# 02_USB2UART.net
KiCad netlist of a schematic drawn in Altium Designer
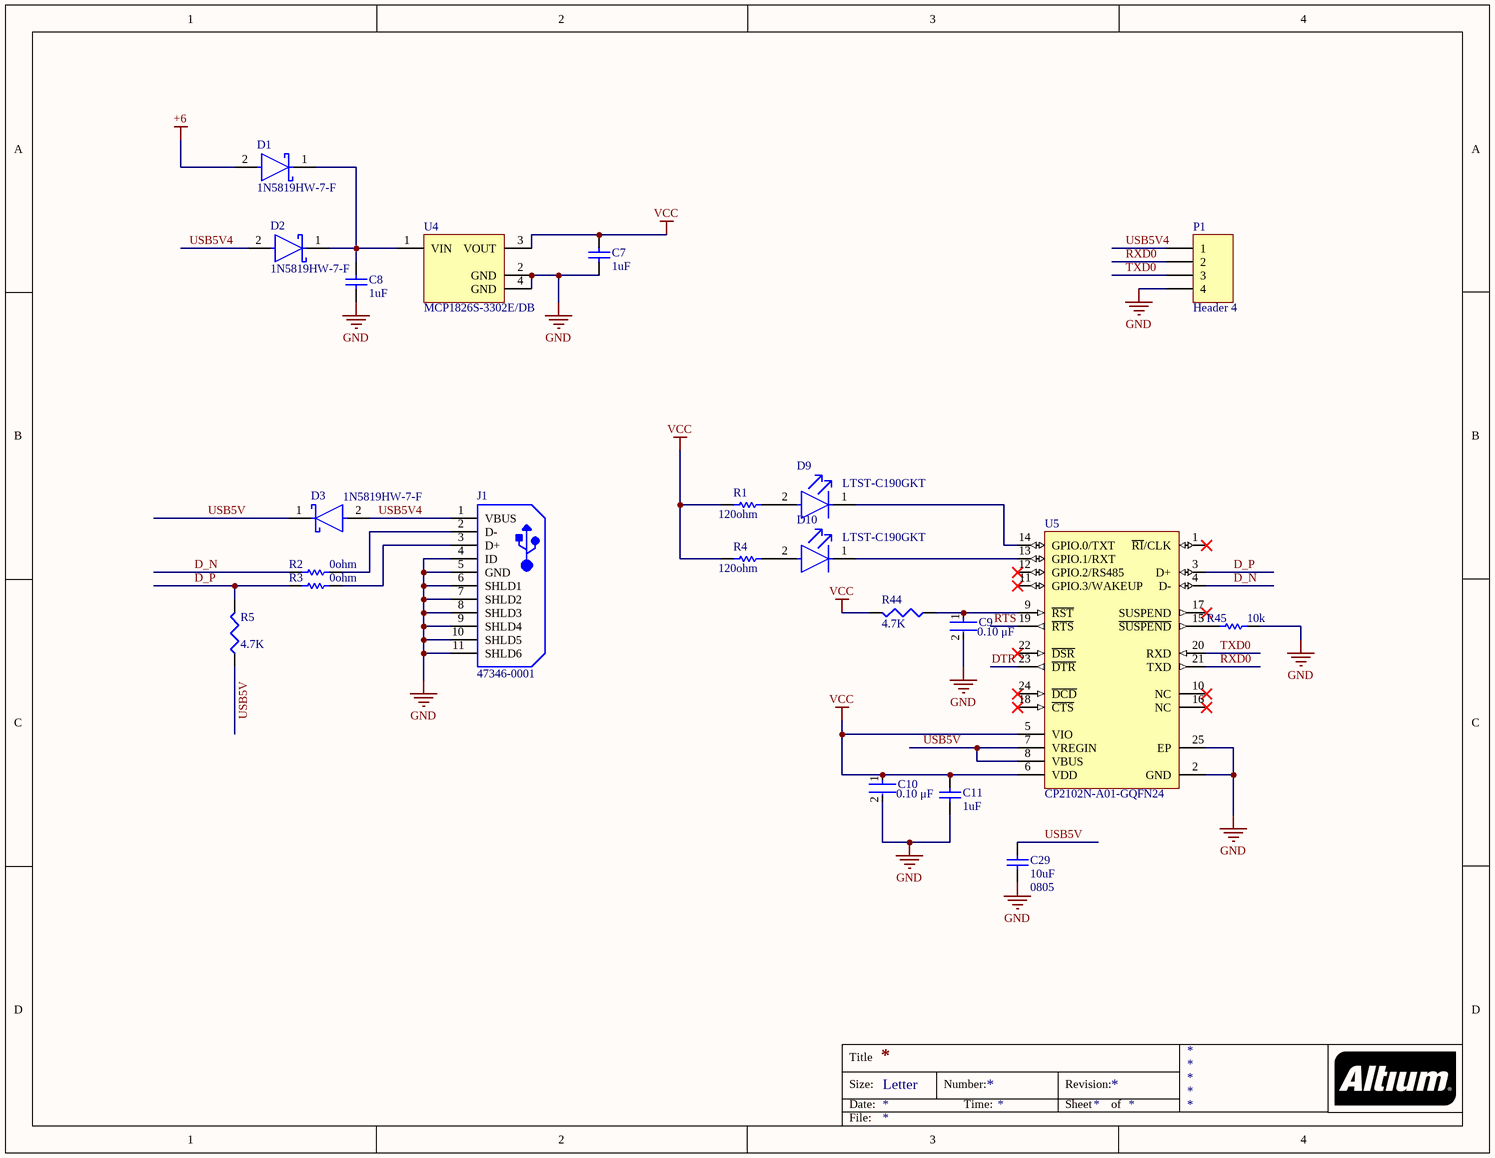
[diagram p0: 02_USB2UART.SchDoc]

(export (version "E")
  (design (tool "Eeschema 10.0.6"))
  (components
    (comp (ref "C7")
      (value "1uF")
      (footprint "CAPC1608X87X35LL15T15")
      (fields (field (name "MANUFACTURER") "Kemet") (field (name "PART NUMBER") "C0603C101J1GACTU"))
      (libsource (lib "Altium Content Vault") (part "CAP"))
    )
    (comp (ref "C8")
      (value "1uF")
      (footprint "CAPC1608X87X35LL15T15")
      (fields (field (name "MANUFACTURER") "Kemet") (field (name "PART NUMBER") "C0603C101J1GACTU"))
      (libsource (lib "Altium Content Vault") (part "CAP"))
    )
    (comp (ref "C9")
      (value "C0603C104M4RAC7411")
      (footprint "FP-C0603C-CF-MFG")
      (description "CAP CER 0.1UF 16V X7R 0603")
      (fields
        (field (name "TOLERANCE") "0.2")
        (field (name "CAPACITANCE") "0.10 μF")
        (field (name "MANUFACTURER") "KEMET")
      )
      (libsource (lib "Altium Content Vault") (part "b4654b650e69147ec39a6b967a45e02"))
    )
    (comp (ref "C10")
      (value "C0603C104M4RAC7411")
      (footprint "FP-C0603C-CF-MFG")
      (description "CAP CER 0.1UF 16V X7R 0603")
      (fields
        (field (name "TOLERANCE") "0.2")
        (field (name "CAPACITANCE") "0.10 μF")
        (field (name "MANUFACTURER") "KEMET")
      )
      (libsource (lib "Altium Content Vault") (part "b4654b650e69147ec39a6b967a45e02"))
    )
    (comp (ref "C11")
      (value "1uF")
      (footprint "CAPC1608X87X35LL15T15")
      (fields (field (name "MANUFACTURER") "Kemet") (field (name "PART NUMBER") "C0603C101J1GACTU"))
      (libsource (lib "Altium Content Vault") (part "CAP"))
    )
    (comp (ref "C29")
      (value "10uF")
      (footprint "CAPC2013X135X50LL10T20")
      (fields
        (field (name "MANUFACTURER") "Murata")
        (field (name "PART NUMBER") "GRM21BR61C106KE15L")
        (field (name "PACKAGE") "0805")
      )
      (libsource (lib "Altium Content Vault") (part "CAP"))
    )
    (comp (ref "D1")
      (value "1N5819HW-7-F")
      (footprint "FP-SOD123-MFG")
      (description "DIODE SCHOTTKY 40V 1A SOD123")
      (fields
        (field (name "OCTOPART") "https://octopart.com/1n5819hw-7-f-diodes+inc.-323197")
        (field (name "MANUFACTURER") "Diodes Inc")
      )
      (libsource (lib "Altium Content Vault") (part "1d6ec82d83fb6aee721767c19dac4b9"))
    )
    (comp (ref "D2")
      (value "1N5819HW-7-F")
      (footprint "FP-SOD123-MFG")
      (description "DIODE SCHOTTKY 40V 1A SOD123")
      (fields
        (field (name "OCTOPART") "https://octopart.com/1n5819hw-7-f-diodes+inc.-323197")
        (field (name "MANUFACTURER") "Diodes Inc")
      )
      (libsource (lib "Altium Content Vault") (part "1d6ec82d83fb6aee721767c19dac4b9"))
    )
    (comp (ref "D3")
      (value "1N5819HW-7-F")
      (footprint "FP-SOD123-MFG")
      (description "DIODE SCHOTTKY 40V 1A SOD123")
      (fields
        (field (name "OCTOPART") "https://octopart.com/1n5819hw-7-f-diodes+inc.-323197")
        (field (name "MANUFACTURER") "Diodes Inc")
      )
      (libsource (lib "Altium Content Vault") (part "1d6ec82d83fb6aee721767c19dac4b9"))
    )
    (comp (ref "D9")
      (value "LTST-C190GKT")
      (footprint "FP-LTST-C190GKT-MFG")
      (description "LED GREEN CLEAR CHIP SMD")
      (fields (field (name "VOLTAGE") "2V"))
      (libsource (lib "Altium Content Vault") (part "8706943c75ba83719d021d2fdc84c58"))
    )
    (comp (ref "D10")
      (value "LTST-C190GKT")
      (footprint "FP-LTST-C190GKT-MFG")
      (description "LED GREEN CLEAR CHIP SMD")
      (fields (field (name "VOLTAGE") "2V"))
      (libsource (lib "Altium Content Vault") (part "8706943c75ba83719d021d2fdc84c58"))
    )
    (comp (ref "J1")
      (value "47346-0001")
      (footprint "MOLX-47346-0001-5_V")
      (description "Micro-USB B Receptacle with Flange, -30 to 85 degC, 5-Pin SMD, RoHS, Tape and Reel")
      (fields (field (name "MANUFACTURER") "Molex"))
      (libsource (lib "Altium Content Vault") (part "MOLX-47346-0001-5"))
    )
    (comp (ref "P1")
      (value "Header 4")
      (footprint "HDR1X4")
      (description "Header, 4-Pin")
      (fields (field (name "PUBLISHER") "Altium Limited"))
      (libsource (lib "Miscellaneous Connectors") (part "Header 4"))
    )
    (comp (ref "R1")
      (value "120ohm")
      (footprint "RESC1608X55X30NL20T20")
      (fields (field (name "PART NUMBER") "ERA-3AEB121V") (field (name "MANUFACTURER") "Panasonic"))
      (libsource (lib "Altium Content Vault") (part "RES"))
    )
    (comp (ref "R2")
      (value "0ohm")
      (footprint "RESC1608X55X25ML10T15")
      (description "Chip Resistor, 0 Ohm, +/- 5%, 0.1 W, -55 to 155 degC, 0603 (1608 Metric), RoHS, Tape and Reel")
      (fields (field (name "TOLERANCE") "5%") (field (name "MANUFACTURER") "Yageo"))
      (libsource (lib "Altium Content Vault") (part "RES-2"))
    )
    (comp (ref "R3")
      (value "0ohm")
      (footprint "RESC1608X55X25ML10T15")
      (description "Chip Resistor, 0 Ohm, +/- 5%, 0.1 W, -55 to 155 degC, 0603 (1608 Metric), RoHS, Tape and Reel")
      (fields (field (name "TOLERANCE") "5%") (field (name "MANUFACTURER") "Yageo"))
      (libsource (lib "Altium Content Vault") (part "RES-2"))
    )
    (comp (ref "R4")
      (value "120ohm")
      (footprint "RESC1608X55X30NL20T20")
      (fields (field (name "PART NUMBER") "ERA-3AEB121V") (field (name "MANUFACTURER") "Panasonic"))
      (libsource (lib "Altium Content Vault") (part "RES"))
    )
    (comp (ref "R5")
      (value "4.7K")
      (footprint "J1-0603")
      (description "Resistor")
      (fields (field (name "Comment") "4.7k") (field (name "PUBLISHER") "Altium Limited"))
      (libsource (lib "Miscellaneous Devices") (part "Res3"))
    )
    (comp (ref "R44")
      (value "4.7K")
      (footprint "J1-0603")
      (description "Resistor")
      (fields (field (name "Comment") "4.7k") (field (name "PUBLISHER") "Altium Limited"))
      (libsource (lib "Miscellaneous Devices") (part "Res3"))
    )
    (comp (ref "R45")
      (value "10k")
      (footprint "RESC1609X55X30LL15T15")
      (description "Chip Resistor, 10 KOhm, +/- 1%, 0.1 W, -55 to 155 degC, 0603 (1608 Metric), RoHS, Tape and Reel")
      (fields (field (name "TOLERANCE") "1%") (field (name "MANUFACTURER") "Panasonic"))
      (libsource (lib "Altium Content Vault") (part "RES-2"))
    )
    (comp (ref "U4")
      (value "MCP1826S-3302E/DB")
      (footprint "SOT-223-DB3_L")
      (description "1000 mA, Low Voltage, Low Quiescent Current LDO Regulator, 3-Pin SOT-223, Extended Temperature")
      (libsource (lib "Altium Content Vault") (part "PM-LINEREG-MCP1826-IL4"))
    )
    (comp (ref "U5")
      (value "CP2102N-A01-GQFN24")
      (footprint "SLAB-QFN-24-2550x2550TP_A_V")
      (description "USBXpress(TM) Family, 4 GPIOs, 2.2 to 3.6 V, -40 to 85 degC, 24-Pin QFN, RoHS")
      (fields (field (name "MANUFACTURER") "Silicon Labs"))
      (libsource (lib "Altium Content Vault") (part "SLAB-CP2102N-QFN-24"))
    )
  )
  (nets
    (net (code "1") (name "+6") (class "Default")
      (node (ref "D1") (pin "2") (pinfunction "A_2") (pintype "passive"))
    )
    (net (code "2") (name "/DTR") (class "Default")
      (node (ref "U5") (pin "23") (pinfunction "~{DTR}_23") (pintype "output"))
    )
    (net (code "3") (name "/D_N") (class "Default")
      (node (ref "R2") (pin "1") (pinfunction "1_1") (pintype "passive"))
      (node (ref "U5") (pin "4") (pinfunction "D-_4") (pintype "bidirectional"))
    )
    (net (code "4") (name "/D_P") (class "Default")
      (node (ref "R3") (pin "1") (pinfunction "1_1") (pintype "passive"))
      (node (ref "R5") (pin "2") (pinfunction "2_2") (pintype "passive"))
      (node (ref "U5") (pin "3") (pinfunction "D+_3") (pintype "bidirectional"))
    )
    (net (code "5") (name "/RTS") (class "Default")
      (node (ref "U5") (pin "19") (pinfunction "~{RTS}_19") (pintype "output"))
    )
    (net (code "6") (name "/RXD0") (class "Default")
      (node (ref "P1") (pin "2") (pinfunction "2_2") (pintype "passive"))
      (node (ref "U5") (pin "21") (pinfunction "TXD_21") (pintype "output"))
    )
    (net (code "7") (name "/TXD0") (class "Default")
      (node (ref "P1") (pin "3") (pinfunction "3_3") (pintype "passive"))
      (node (ref "U5") (pin "20") (pinfunction "RXD_20") (pintype "input"))
    )
    (net (code "8") (name "/USB5V") (class "Default")
      (node (ref "C29") (pin "2") (pinfunction "2_2") (pintype "passive"))
      (node (ref "D3") (pin "1") (pinfunction "C_1") (pintype "passive"))
      (node (ref "R5") (pin "1") (pinfunction "1_1") (pintype "passive"))
      (node (ref "U5") (pin "7") (pinfunction "VREGIN_7") (pintype "power_in"))
      (node (ref "U5") (pin "8") (pinfunction "VBUS_8") (pintype "power_in"))
    )
    (net (code "9") (name "/USB5V4") (class "Default")
      (node (ref "D2") (pin "2") (pinfunction "A_2") (pintype "passive"))
      (node (ref "D3") (pin "2") (pinfunction "A_2") (pintype "passive"))
      (node (ref "J1") (pin "1") (pinfunction "VBUS_1") (pintype "passive"))
      (node (ref "P1") (pin "1") (pinfunction "1_1") (pintype "passive"))
    )
    (net (code "10") (name "GND") (class "Default")
      (node (ref "C10") (pin "2") (pinfunction "2_2") (pintype "passive"))
      (node (ref "C11") (pin "1") (pinfunction "1_1") (pintype "passive"))
      (node (ref "C29") (pin "1") (pinfunction "1_1") (pintype "passive"))
      (node (ref "C7") (pin "1") (pinfunction "1_1") (pintype "passive"))
      (node (ref "C8") (pin "1") (pinfunction "1_1") (pintype "passive"))
      (node (ref "C9") (pin "2") (pinfunction "2_2") (pintype "passive"))
      (node (ref "J1") (pin "10") (pinfunction "SHLD5_10") (pintype "passive"))
      (node (ref "J1") (pin "11") (pinfunction "SHLD6_11") (pintype "passive"))
      (node (ref "J1") (pin "4") (pinfunction "ID_4") (pintype "passive"))
      (node (ref "J1") (pin "5") (pinfunction "GND_5") (pintype "passive"))
      (node (ref "J1") (pin "6") (pinfunction "SHLD1_6") (pintype "passive"))
      (node (ref "J1") (pin "7") (pinfunction "SHLD2_7") (pintype "passive"))
      (node (ref "J1") (pin "8") (pinfunction "SHLD3_8") (pintype "passive"))
      (node (ref "J1") (pin "9") (pinfunction "SHLD4_9") (pintype "passive"))
      (node (ref "P1") (pin "4") (pinfunction "4_4") (pintype "passive"))
      (node (ref "R45") (pin "2") (pinfunction "2_2") (pintype "passive"))
      (node (ref "U4") (pin "2") (pinfunction "GND_2") (pintype "power_in"))
      (node (ref "U4") (pin "4") (pinfunction "GND_4") (pintype "power_in"))
      (node (ref "U5") (pin "2") (pinfunction "GND_2") (pintype "power_in"))
      (node (ref "U5") (pin "25") (pinfunction "EP_25") (pintype "power_in"))
    )
    (net (code "11") (name "Net-(D1-C)") (class "Default")
      (node (ref "C8") (pin "2") (pinfunction "2_2") (pintype "passive"))
      (node (ref "D1") (pin "1") (pinfunction "C_1") (pintype "passive"))
      (node (ref "D2") (pin "1") (pinfunction "C_1") (pintype "passive"))
      (node (ref "U4") (pin "1") (pinfunction "VIN_1") (pintype "power_in"))
    )
    (net (code "12") (name "Net-(D9-A)") (class "Default")
      (node (ref "D9") (pin "2") (pinfunction "A_2") (pintype "passive"))
      (node (ref "R1") (pin "2") (pinfunction "2_2") (pintype "passive"))
    )
    (net (code "13") (name "Net-(D9-C)") (class "Default")
      (node (ref "D9") (pin "1") (pinfunction "C_1") (pintype "passive"))
      (node (ref "U5") (pin "14") (pinfunction "GPIO.0/TXT_14") (pintype "bidirectional"))
    )
    (net (code "14") (name "Net-(D10-A)") (class "Default")
      (node (ref "D10") (pin "2") (pinfunction "A_2") (pintype "passive"))
      (node (ref "R4") (pin "2") (pinfunction "2_2") (pintype "passive"))
    )
    (net (code "15") (name "Net-(D10-C)") (class "Default")
      (node (ref "D10") (pin "1") (pinfunction "C_1") (pintype "passive"))
      (node (ref "U5") (pin "13") (pinfunction "GPIO.1/RXT_13") (pintype "bidirectional"))
    )
    (net (code "16") (name "Net-(J1-D+)") (class "Default")
      (node (ref "J1") (pin "3") (pinfunction "D+_3") (pintype "passive"))
      (node (ref "R3") (pin "2") (pinfunction "2_2") (pintype "passive"))
    )
    (net (code "17") (name "Net-(J1-D-)") (class "Default")
      (node (ref "J1") (pin "2") (pinfunction "D-_2") (pintype "passive"))
      (node (ref "R2") (pin "2") (pinfunction "2_2") (pintype "passive"))
    )
    (net (code "18") (name "Net-(U5-~{RST})") (class "Default")
      (node (ref "C9") (pin "1") (pinfunction "1_1") (pintype "passive"))
      (node (ref "R44") (pin "1") (pinfunction "1_1") (pintype "passive"))
      (node (ref "U5") (pin "9") (pinfunction "~{RST}_9") (pintype "input"))
    )
    (net (code "19") (name "Net-(U5-~{SUSPEND})") (class "Default")
      (node (ref "R45") (pin "1") (pinfunction "1_1") (pintype "passive"))
      (node (ref "U5") (pin "15") (pinfunction "~{SUSPEND}_15") (pintype "output"))
    )
    (net (code "20") (name "VCC") (class "Default")
      (node (ref "C10") (pin "1") (pinfunction "1_1") (pintype "passive"))
      (node (ref "C11") (pin "2") (pinfunction "2_2") (pintype "passive"))
      (node (ref "C7") (pin "2") (pinfunction "2_2") (pintype "passive"))
      (node (ref "R1") (pin "1") (pinfunction "1_1") (pintype "passive"))
      (node (ref "R4") (pin "1") (pinfunction "1_1") (pintype "passive"))
      (node (ref "R44") (pin "2") (pinfunction "2_2") (pintype "passive"))
      (node (ref "U4") (pin "3") (pinfunction "VOUT_3") (pintype "power_in"))
      (node (ref "U5") (pin "5") (pinfunction "VIO_5") (pintype "power_in"))
      (node (ref "U5") (pin "6") (pinfunction "VDD_6") (pintype "power_in"))
    )
    (net (code "21") (name "unconnected-(U5-GPIO.2{slash}RS485-Pad12)") (class "Default")
      (node (ref "U5") (pin "12") (pinfunction "GPIO.2/RS485_12") (pintype "bidirectional+no_connect"))
    )
    (net (code "22") (name "unconnected-(U5-GPIO.3{slash}WAKEUP-Pad11)") (class "Default")
      (node (ref "U5") (pin "11") (pinfunction "GPIO.3/WAKEUP_11") (pintype "bidirectional+no_connect"))
    )
    (net (code "23") (name "unconnected-(U5-NC-Pad10)") (class "Default")
      (node (ref "U5") (pin "10") (pinfunction "NC_10") (pintype "passive+no_connect"))
    )
    (net (code "24") (name "unconnected-(U5-NC-Pad16)") (class "Default")
      (node (ref "U5") (pin "16") (pinfunction "NC_16") (pintype "passive+no_connect"))
    )
    (net (code "25") (name "unconnected-(U5-SUSPEND-Pad17)") (class "Default")
      (node (ref "U5") (pin "17") (pinfunction "SUSPEND_17") (pintype "output+no_connect"))
    )
    (net (code "26") (name "unconnected-(U5-~{CTS}-Pad18)") (class "Default")
      (node (ref "U5") (pin "18") (pinfunction "~{CTS}_18") (pintype "input+no_connect"))
    )
    (net (code "27") (name "unconnected-(U5-~{DCD}-Pad24)") (class "Default")
      (node (ref "U5") (pin "24") (pinfunction "~{DCD}_24") (pintype "input+no_connect"))
    )
    (net (code "28") (name "unconnected-(U5-~{DSR}-Pad22)") (class "Default")
      (node (ref "U5") (pin "22") (pinfunction "~{DSR}_22") (pintype "input+no_connect"))
    )
    (net (code "29") (name "unconnected-(U5-~{RI}{slash}CLK-Pad1)") (class "Default")
      (node (ref "U5") (pin "1") (pinfunction "~{RI}/CLK_1") (pintype "bidirectional+no_connect"))
    )
  )
)
